# OperantFEDv7.net
KiCad netlist of a schematic drawn in EAGLE
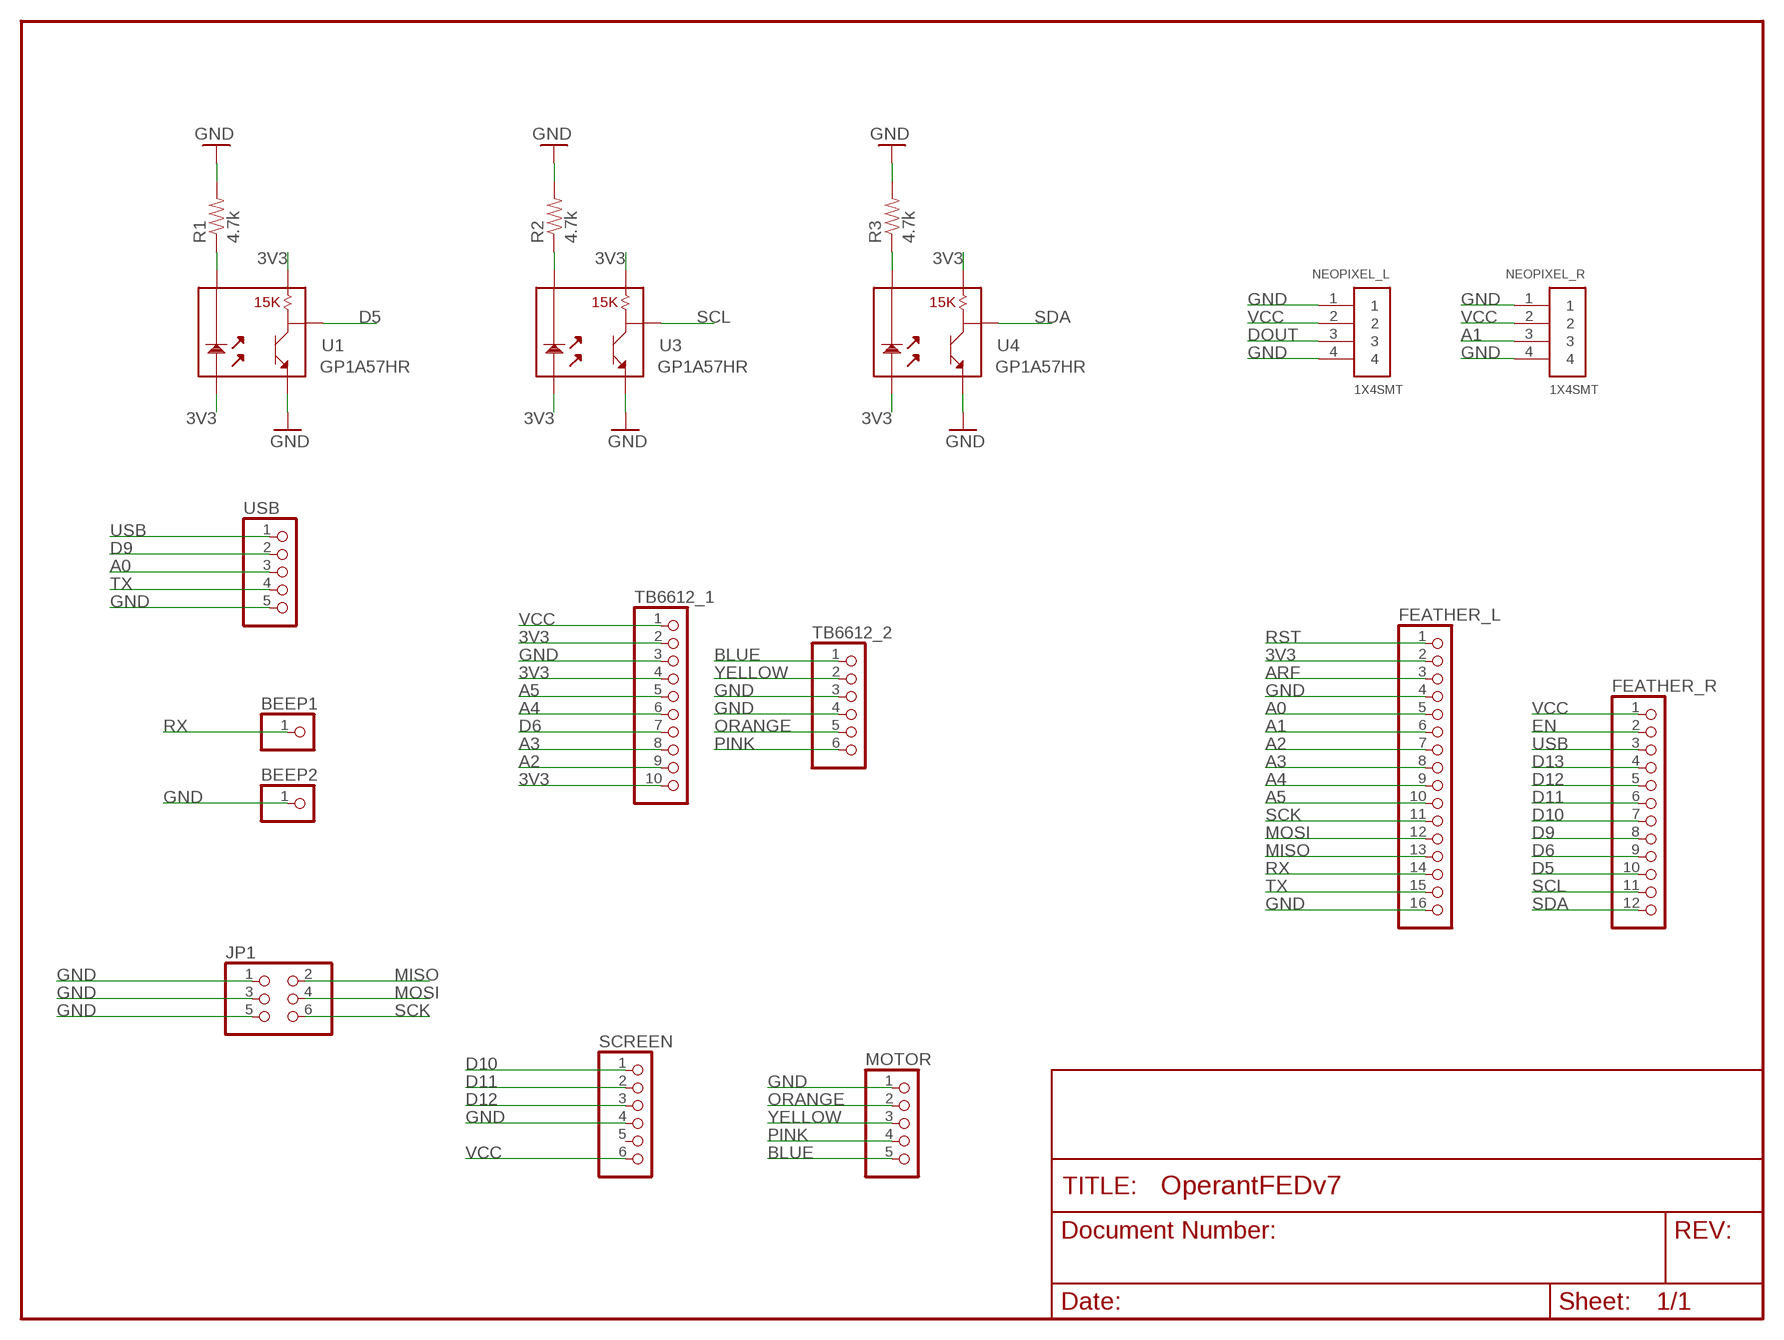
[diagram p0: schematic, sheet 1]

(export (version "E")
  (design (tool "Eeschema 10.0.6"))
  (components
    (comp (ref "BEEP1")
      (value "PINHD-1X1")
      (footprint "eagle-import:1X01")
      (libsource (lib "eagle-import") (part "PINHD-1X1"))
    )
    (comp (ref "BEEP2")
      (value "PINHD-1X1")
      (footprint "eagle-import:1X01")
      (libsource (lib "eagle-import") (part "PINHD-1X1"))
    )
    (comp (ref "FEATHER_L")
      (value "PINHD-1X16")
      (footprint "eagle-import:1X16")
      (libsource (lib "eagle-import") (part "PINHD-1X16"))
    )
    (comp (ref "FEATHER_R")
      (value "PINHD-1X12")
      (footprint "eagle-import:1X12")
      (libsource (lib "eagle-import") (part "PINHD-1X12"))
    )
    (comp (ref "JP1")
      (value "PINHD-2X3")
      (footprint "eagle-import:2X03")
      (libsource (lib "eagle-import") (part "PINHD-2X3"))
    )
    (comp (ref "MOTOR")
      (value "PINHD-1X5")
      (footprint "eagle-import:1X05")
      (libsource (lib "eagle-import") (part "PINHD-1X5"))
    )
    (comp (ref "NEOPIXEL_L")
      (value "1X4SMT")
      (footprint "eagle-import:1X4-SMT")
      (libsource (lib "eagle-import") (part "1X4SMT"))
    )
    (comp (ref "NEOPIXEL_R")
      (value "1X4SMT")
      (footprint "eagle-import:1X4-SMT")
      (libsource (lib "eagle-import") (part "1X4SMT"))
    )
    (comp (ref "R1")
      (value "4.7k")
      (footprint "eagle-import:AXIAL-0.3")
      (libsource (lib "eagle-import") (part "RESISTORPTH1"))
    )
    (comp (ref "R2")
      (value "4.7k")
      (footprint "eagle-import:AXIAL-0.3")
      (libsource (lib "eagle-import") (part "RESISTORPTH1"))
    )
    (comp (ref "R3")
      (value "4.7k")
      (footprint "eagle-import:AXIAL-0.3")
      (libsource (lib "eagle-import") (part "RESISTORPTH1"))
    )
    (comp (ref "SCREEN")
      (value "PINHD-1X6")
      (footprint "eagle-import:1X06")
      (libsource (lib "eagle-import") (part "PINHD-1X6"))
    )
    (comp (ref "TB6612_1")
      (value "PINHD-1X10")
      (footprint "eagle-import:1X10")
      (libsource (lib "eagle-import") (part "PINHD-1X10"))
    )
    (comp (ref "TB6612_2")
      (value "PINHD-1X6")
      (footprint "eagle-import:1X06")
      (libsource (lib "eagle-import") (part "PINHD-1X6"))
    )
    (comp (ref "U1")
      (value "GP1A57HR")
      (footprint "eagle-import:GP1A57HR")
      (libsource (lib "eagle-import") (part "GP1A57HR"))
    )
    (comp (ref "U3")
      (value "GP1A57HR")
      (footprint "eagle-import:GP1A57HR")
      (libsource (lib "eagle-import") (part "GP1A57HR"))
    )
    (comp (ref "U4")
      (value "GP1A57HR")
      (footprint "eagle-import:GP1A57HR")
      (libsource (lib "eagle-import") (part "GP1A57HR"))
    )
    (comp (ref "USB")
      (value "PINHD-1X5")
      (footprint "eagle-import:1X05")
      (libsource (lib "eagle-import") (part "PINHD-1X5"))
    )
  )
  (nets
    (net (code "1") (name "/3V3") (class "Default")
      (node (ref "FEATHER_L") (pin "2") (pinfunction "2_2") (pintype "passive"))
      (node (ref "TB6612_1") (pin "10") (pinfunction "10_10") (pintype "passive"))
      (node (ref "TB6612_1") (pin "2") (pinfunction "2_2") (pintype "passive"))
      (node (ref "TB6612_1") (pin "4") (pinfunction "4_4") (pintype "passive"))
      (node (ref "U1") (pin "1") (pinfunction "1_1") (pintype "bidirectional"))
      (node (ref "U1") (pin "3") (pinfunction "3_3") (pintype "bidirectional"))
      (node (ref "U3") (pin "1") (pinfunction "1_1") (pintype "bidirectional"))
      (node (ref "U3") (pin "3") (pinfunction "3_3") (pintype "bidirectional"))
      (node (ref "U4") (pin "1") (pinfunction "1_1") (pintype "bidirectional"))
      (node (ref "U4") (pin "3") (pinfunction "3_3") (pintype "bidirectional"))
    )
    (net (code "2") (name "/A0") (class "Default")
      (node (ref "FEATHER_L") (pin "5") (pinfunction "5_5") (pintype "passive"))
      (node (ref "USB") (pin "3") (pinfunction "3_3") (pintype "passive"))
    )
    (net (code "3") (name "/A1") (class "Default")
      (node (ref "FEATHER_L") (pin "6") (pinfunction "6_6") (pintype "passive"))
      (node (ref "NEOPIXEL_R") (pin "3") (pinfunction "3_3") (pintype "bidirectional"))
    )
    (net (code "4") (name "/A2") (class "Default")
      (node (ref "FEATHER_L") (pin "7") (pinfunction "7_7") (pintype "passive"))
      (node (ref "TB6612_1") (pin "9") (pinfunction "9_9") (pintype "passive"))
    )
    (net (code "5") (name "/A3") (class "Default")
      (node (ref "FEATHER_L") (pin "8") (pinfunction "8_8") (pintype "passive"))
      (node (ref "TB6612_1") (pin "8") (pinfunction "8_8") (pintype "passive"))
    )
    (net (code "6") (name "/A4") (class "Default")
      (node (ref "FEATHER_L") (pin "9") (pinfunction "9_9") (pintype "passive"))
      (node (ref "TB6612_1") (pin "6") (pinfunction "6_6") (pintype "passive"))
    )
    (net (code "7") (name "/A5") (class "Default")
      (node (ref "FEATHER_L") (pin "10") (pinfunction "10_10") (pintype "passive"))
      (node (ref "TB6612_1") (pin "5") (pinfunction "5_5") (pintype "passive"))
    )
    (net (code "8") (name "/ARF") (class "Default")
      (node (ref "FEATHER_L") (pin "3") (pinfunction "3_3") (pintype "passive"))
    )
    (net (code "9") (name "/BLUE") (class "Default")
      (node (ref "MOTOR") (pin "5") (pinfunction "5_5") (pintype "passive"))
      (node (ref "TB6612_2") (pin "1") (pinfunction "1_1") (pintype "passive"))
    )
    (net (code "10") (name "/D5") (class "Default")
      (node (ref "FEATHER_R") (pin "10") (pinfunction "10_10") (pintype "passive"))
      (node (ref "U1") (pin "4") (pinfunction "4_4") (pintype "bidirectional"))
    )
    (net (code "11") (name "/D6") (class "Default")
      (node (ref "FEATHER_R") (pin "9") (pinfunction "9_9") (pintype "passive"))
      (node (ref "TB6612_1") (pin "7") (pinfunction "7_7") (pintype "passive"))
    )
    (net (code "12") (name "/D9") (class "Default")
      (node (ref "FEATHER_R") (pin "8") (pinfunction "8_8") (pintype "passive"))
      (node (ref "USB") (pin "2") (pinfunction "2_2") (pintype "passive"))
    )
    (net (code "13") (name "/D10") (class "Default")
      (node (ref "FEATHER_R") (pin "7") (pinfunction "7_7") (pintype "passive"))
      (node (ref "SCREEN") (pin "1") (pinfunction "1_1") (pintype "passive"))
    )
    (net (code "14") (name "/D11") (class "Default")
      (node (ref "FEATHER_R") (pin "6") (pinfunction "6_6") (pintype "passive"))
      (node (ref "SCREEN") (pin "2") (pinfunction "2_2") (pintype "passive"))
    )
    (net (code "15") (name "/D12") (class "Default")
      (node (ref "FEATHER_R") (pin "5") (pinfunction "5_5") (pintype "passive"))
      (node (ref "SCREEN") (pin "3") (pinfunction "3_3") (pintype "passive"))
    )
    (net (code "16") (name "/D13") (class "Default")
      (node (ref "FEATHER_R") (pin "4") (pinfunction "4_4") (pintype "passive"))
    )
    (net (code "17") (name "/DOUT") (class "Default")
      (node (ref "NEOPIXEL_L") (pin "3") (pinfunction "3_3") (pintype "bidirectional"))
    )
    (net (code "18") (name "/EN") (class "Default")
      (node (ref "FEATHER_R") (pin "2") (pinfunction "2_2") (pintype "passive"))
    )
    (net (code "19") (name "/MISO") (class "Default")
      (node (ref "FEATHER_L") (pin "13") (pinfunction "13_13") (pintype "passive"))
      (node (ref "JP1") (pin "2") (pinfunction "2_2") (pintype "passive"))
    )
    (net (code "20") (name "/MOSI") (class "Default")
      (node (ref "FEATHER_L") (pin "12") (pinfunction "12_12") (pintype "passive"))
      (node (ref "JP1") (pin "4") (pinfunction "4_4") (pintype "passive"))
    )
    (net (code "21") (name "/ORANGE") (class "Default")
      (node (ref "MOTOR") (pin "2") (pinfunction "2_2") (pintype "passive"))
      (node (ref "TB6612_2") (pin "5") (pinfunction "5_5") (pintype "passive"))
    )
    (net (code "22") (name "/PINK") (class "Default")
      (node (ref "MOTOR") (pin "4") (pinfunction "4_4") (pintype "passive"))
      (node (ref "TB6612_2") (pin "6") (pinfunction "6_6") (pintype "passive"))
    )
    (net (code "23") (name "/RST") (class "Default")
      (node (ref "FEATHER_L") (pin "1") (pinfunction "1_1") (pintype "passive"))
    )
    (net (code "24") (name "/RX") (class "Default")
      (node (ref "BEEP1") (pin "1") (pinfunction "1_1") (pintype "passive"))
      (node (ref "FEATHER_L") (pin "14") (pinfunction "14_14") (pintype "passive"))
    )
    (net (code "25") (name "/SCK") (class "Default")
      (node (ref "FEATHER_L") (pin "11") (pinfunction "11_11") (pintype "passive"))
      (node (ref "JP1") (pin "6") (pinfunction "6_6") (pintype "passive"))
    )
    (net (code "26") (name "/SCL") (class "Default")
      (node (ref "FEATHER_R") (pin "11") (pinfunction "11_11") (pintype "passive"))
      (node (ref "U3") (pin "4") (pinfunction "4_4") (pintype "bidirectional"))
    )
    (net (code "27") (name "/SDA") (class "Default")
      (node (ref "FEATHER_R") (pin "12") (pinfunction "12_12") (pintype "passive"))
      (node (ref "U4") (pin "4") (pinfunction "4_4") (pintype "bidirectional"))
    )
    (net (code "28") (name "/TX") (class "Default")
      (node (ref "FEATHER_L") (pin "15") (pinfunction "15_15") (pintype "passive"))
      (node (ref "USB") (pin "4") (pinfunction "4_4") (pintype "passive"))
    )
    (net (code "29") (name "/USB") (class "Default")
      (node (ref "FEATHER_R") (pin "3") (pinfunction "3_3") (pintype "passive"))
      (node (ref "USB") (pin "1") (pinfunction "1_1") (pintype "passive"))
    )
    (net (code "30") (name "/VCC") (class "Default")
      (node (ref "FEATHER_R") (pin "1") (pinfunction "1_1") (pintype "passive"))
      (node (ref "NEOPIXEL_L") (pin "2") (pinfunction "2_2") (pintype "bidirectional"))
      (node (ref "NEOPIXEL_R") (pin "2") (pinfunction "2_2") (pintype "bidirectional"))
      (node (ref "SCREEN") (pin "6") (pinfunction "6_6") (pintype "passive"))
      (node (ref "TB6612_1") (pin "1") (pinfunction "1_1") (pintype "passive"))
    )
    (net (code "31") (name "/YELLOW") (class "Default")
      (node (ref "MOTOR") (pin "3") (pinfunction "3_3") (pintype "passive"))
      (node (ref "TB6612_2") (pin "2") (pinfunction "2_2") (pintype "passive"))
    )
    (net (code "32") (name "GND") (class "Default")
      (node (ref "BEEP2") (pin "1") (pinfunction "1_1") (pintype "passive"))
      (node (ref "FEATHER_L") (pin "16") (pinfunction "16_16") (pintype "passive"))
      (node (ref "FEATHER_L") (pin "4") (pinfunction "4_4") (pintype "passive"))
      (node (ref "JP1") (pin "1") (pinfunction "1_1") (pintype "passive"))
      (node (ref "JP1") (pin "3") (pinfunction "3_3") (pintype "passive"))
      (node (ref "JP1") (pin "5") (pinfunction "5_5") (pintype "passive"))
      (node (ref "MOTOR") (pin "1") (pinfunction "1_1") (pintype "passive"))
      (node (ref "NEOPIXEL_L") (pin "1") (pinfunction "1_1") (pintype "bidirectional"))
      (node (ref "NEOPIXEL_L") (pin "4") (pinfunction "4_4") (pintype "bidirectional"))
      (node (ref "NEOPIXEL_R") (pin "1") (pinfunction "1_1") (pintype "bidirectional"))
      (node (ref "NEOPIXEL_R") (pin "4") (pinfunction "4_4") (pintype "bidirectional"))
      (node (ref "R1") (pin "P$2") (pinfunction "2_P$2") (pintype "passive"))
      (node (ref "R2") (pin "P$2") (pinfunction "2_P$2") (pintype "passive"))
      (node (ref "R3") (pin "P$2") (pinfunction "2_P$2") (pintype "passive"))
      (node (ref "SCREEN") (pin "4") (pinfunction "4_4") (pintype "passive"))
      (node (ref "TB6612_1") (pin "3") (pinfunction "3_3") (pintype "passive"))
      (node (ref "TB6612_2") (pin "3") (pinfunction "3_3") (pintype "passive"))
      (node (ref "TB6612_2") (pin "4") (pinfunction "4_4") (pintype "passive"))
      (node (ref "U1") (pin "5") (pinfunction "5_5") (pintype "bidirectional"))
      (node (ref "U3") (pin "5") (pinfunction "5_5") (pintype "bidirectional"))
      (node (ref "U4") (pin "5") (pinfunction "5_5") (pintype "bidirectional"))
      (node (ref "USB") (pin "5") (pinfunction "5_5") (pintype "passive"))
    )
    (net (code "33") (name "Net-(R1-1)") (class "Default")
      (node (ref "R1") (pin "P$1") (pinfunction "1_P$1") (pintype "passive"))
      (node (ref "U1") (pin "2") (pinfunction "2_2") (pintype "bidirectional"))
    )
    (net (code "34") (name "Net-(R2-1)") (class "Default")
      (node (ref "R2") (pin "P$1") (pinfunction "1_P$1") (pintype "passive"))
      (node (ref "U3") (pin "2") (pinfunction "2_2") (pintype "bidirectional"))
    )
    (net (code "35") (name "Net-(R3-1)") (class "Default")
      (node (ref "R3") (pin "P$1") (pinfunction "1_P$1") (pintype "passive"))
      (node (ref "U4") (pin "2") (pinfunction "2_2") (pintype "bidirectional"))
    )
    (net (code "36") (name "unconnected-(SCREEN-Pad5)") (class "Default")
      (node (ref "SCREEN") (pin "5") (pinfunction "5_5") (pintype "passive"))
    )
  )
)
